# Clock.net
KiCad netlist of a schematic drawn in EAGLE
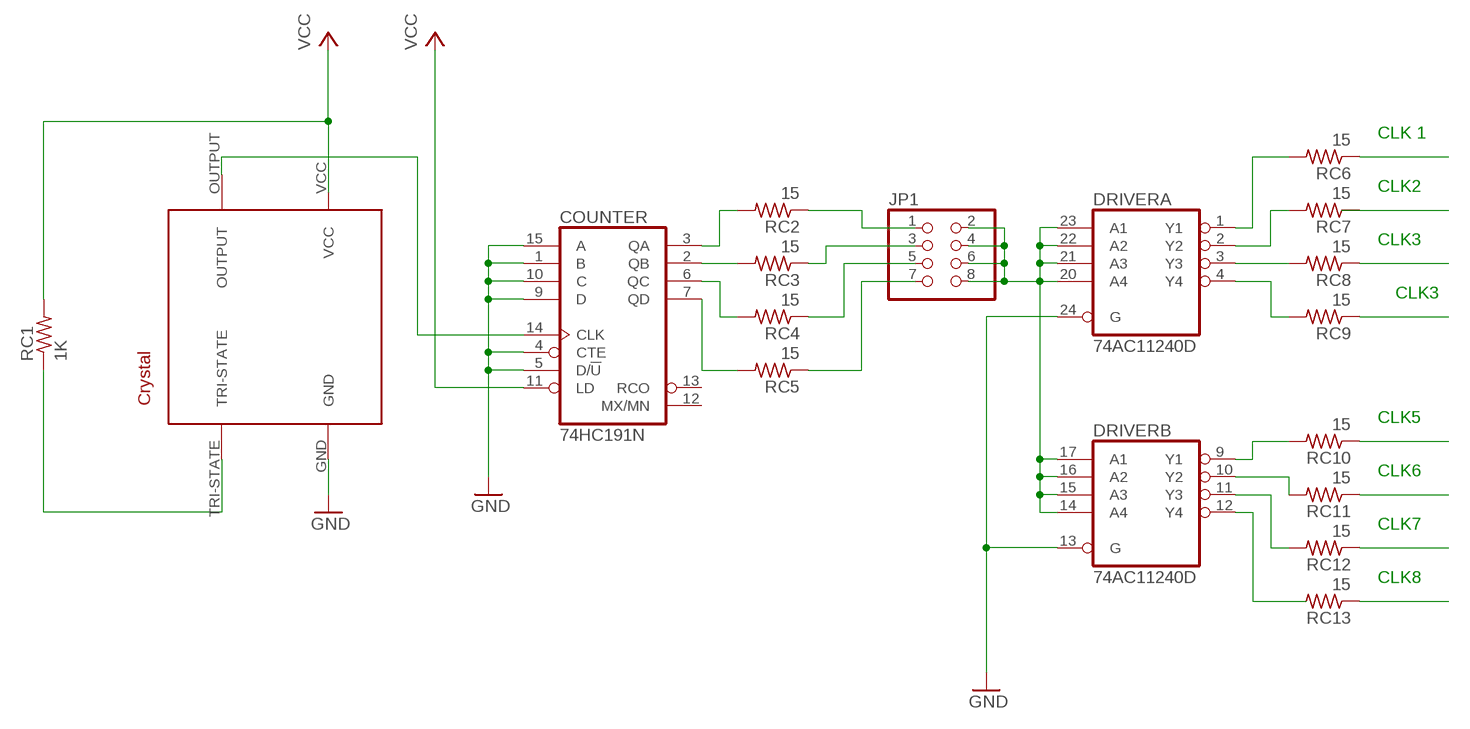
[diagram p0: schematic, sheet 1]

(export (version "E")
  (design (tool "Eeschema 10.0.6"))
  (components
    (comp (ref "COUNTER")
      (value "74HC191N")
      (footprint "eagle-import:DIL16")
      (libsource (lib "eagle-import") (part "74191NHC"))
    )
    (comp (ref "DRIVER")
      (value "74AC11240D")
      (footprint "eagle-import:SO24W")
      (libsource (lib "eagle-import") (part "74AC11240D"))
    )
    (comp (ref "JP1")
      (value "PINHD-2X4")
      (footprint "eagle-import:2X04")
      (libsource (lib "eagle-import") (part "PINHD-2X4"))
    )
    (comp (ref "RC1")
      (value "1K")
      (footprint "eagle-import:R0805")
      (libsource (lib "eagle-import") (part "R-US_R0805"))
    )
    (comp (ref "RC2")
      (value "15")
      (footprint "eagle-import:R0805")
      (libsource (lib "eagle-import") (part "R-US_R0805"))
    )
    (comp (ref "RC3")
      (value "15")
      (footprint "eagle-import:R0805")
      (libsource (lib "eagle-import") (part "R-US_R0805"))
    )
    (comp (ref "RC4")
      (value "15")
      (footprint "eagle-import:R0805")
      (libsource (lib "eagle-import") (part "R-US_R0805"))
    )
    (comp (ref "RC5")
      (value "15")
      (footprint "eagle-import:R0805")
      (libsource (lib "eagle-import") (part "R-US_R0805"))
    )
    (comp (ref "RC6")
      (value "15")
      (footprint "eagle-import:R0805")
      (libsource (lib "eagle-import") (part "R-US_R0805"))
    )
    (comp (ref "RC7")
      (value "15")
      (footprint "eagle-import:R0805")
      (libsource (lib "eagle-import") (part "R-US_R0805"))
    )
    (comp (ref "RC8")
      (value "15")
      (footprint "eagle-import:R0805")
      (libsource (lib "eagle-import") (part "R-US_R0805"))
    )
    (comp (ref "RC9")
      (value "15")
      (footprint "eagle-import:R0805")
      (libsource (lib "eagle-import") (part "R-US_R0805"))
    )
    (comp (ref "RC10")
      (value "15")
      (footprint "eagle-import:R0805")
      (libsource (lib "eagle-import") (part "R-US_R0805"))
    )
    (comp (ref "RC11")
      (value "15")
      (footprint "eagle-import:R0805")
      (libsource (lib "eagle-import") (part "R-US_R0805"))
    )
    (comp (ref "RC12")
      (value "15")
      (footprint "eagle-import:R0805")
      (libsource (lib "eagle-import") (part "R-US_R0805"))
    )
    (comp (ref "RC13")
      (value "15")
      (footprint "eagle-import:R0805")
      (libsource (lib "eagle-import") (part "R-US_R0805"))
    )
    (comp (ref "U$1")
      (value "ECS-8FX")
      (footprint "eagle-import:ECS-8FX")
      (libsource (lib "eagle-import") (part "ECS-8FX"))
    )
  )
  (nets
    (net (code "1") (name "GND") (class "Default")
      (node (ref "COUNTER") (pin "1") (pinfunction "B_1") (pintype "input"))
      (node (ref "COUNTER") (pin "10") (pinfunction "C_10") (pintype "input"))
      (node (ref "COUNTER") (pin "15") (pinfunction "A_15") (pintype "input"))
      (node (ref "COUNTER") (pin "4") (pinfunction "CTE_4") (pintype "input"))
      (node (ref "COUNTER") (pin "5") (pinfunction "D/~{U}_5") (pintype "input"))
      (node (ref "COUNTER") (pin "9") (pinfunction "D_9") (pintype "input"))
      (node (ref "DRIVER") (pin "13") (pinfunction "G_13") (pintype "input"))
      (node (ref "DRIVER") (pin "24") (pinfunction "G_24") (pintype "input"))
      (node (ref "U$1") (pin "GND") (pinfunction "GND_GND") (pintype "bidirectional"))
    )
    (net (code "2") (name "Net-(COUNTERA-CLK)") (class "Default")
      (node (ref "COUNTER") (pin "14") (pinfunction "CLK_14") (pintype "input"))
      (node (ref "U$1") (pin "OUTPUT") (pinfunction "OUTPUT_OUTPUT") (pintype "bidirectional"))
    )
    (net (code "3") (name "Net-(COUNTERA-QA)") (class "Default")
      (node (ref "COUNTER") (pin "3") (pinfunction "QA_3") (pintype "output"))
      (node (ref "RC2") (pin "2") (pinfunction "2_2") (pintype "passive"))
    )
    (net (code "4") (name "Net-(COUNTERA-QB)") (class "Default")
      (node (ref "COUNTER") (pin "2") (pinfunction "QB_2") (pintype "output"))
      (node (ref "RC3") (pin "2") (pinfunction "2_2") (pintype "passive"))
    )
    (net (code "5") (name "Net-(COUNTERA-QC)") (class "Default")
      (node (ref "COUNTER") (pin "6") (pinfunction "QC_6") (pintype "output"))
      (node (ref "RC4") (pin "2") (pinfunction "2_2") (pintype "passive"))
    )
    (net (code "6") (name "Net-(COUNTERA-QD)") (class "Default")
      (node (ref "COUNTER") (pin "7") (pinfunction "QD_7") (pintype "output"))
      (node (ref "RC5") (pin "2") (pinfunction "2_2") (pintype "passive"))
    )
    (net (code "7") (name "Net-(DRIVERA-A1)") (class "Default")
      (node (ref "DRIVER") (pin "14") (pinfunction "A4_14") (pintype "input"))
      (node (ref "DRIVER") (pin "15") (pinfunction "A3_15") (pintype "input"))
      (node (ref "DRIVER") (pin "16") (pinfunction "A2_16") (pintype "input"))
      (node (ref "DRIVER") (pin "17") (pinfunction "A1_17") (pintype "input"))
      (node (ref "DRIVER") (pin "20") (pinfunction "A4_20") (pintype "input"))
      (node (ref "DRIVER") (pin "21") (pinfunction "A3_21") (pintype "input"))
      (node (ref "DRIVER") (pin "22") (pinfunction "A2_22") (pintype "input"))
      (node (ref "DRIVER") (pin "23") (pinfunction "A1_23") (pintype "input"))
      (node (ref "JP1") (pin "2") (pinfunction "2_2") (pintype "passive"))
      (node (ref "JP1") (pin "4") (pinfunction "4_4") (pintype "passive"))
      (node (ref "JP1") (pin "6") (pinfunction "6_6") (pintype "passive"))
      (node (ref "JP1") (pin "8") (pinfunction "8_8") (pintype "passive"))
    )
    (net (code "8") (name "Net-(DRIVERA-Y1)") (class "Default")
      (node (ref "DRIVER") (pin "1") (pinfunction "Y1_1") (pintype "tri_state"))
      (node (ref "RC6") (pin "2") (pinfunction "2_2") (pintype "passive"))
    )
    (net (code "9") (name "Net-(DRIVERA-Y2)") (class "Default")
      (node (ref "DRIVER") (pin "2") (pinfunction "Y2_2") (pintype "tri_state"))
      (node (ref "RC7") (pin "2") (pinfunction "2_2") (pintype "passive"))
    )
    (net (code "10") (name "Net-(DRIVERA-Y3)") (class "Default")
      (node (ref "DRIVER") (pin "3") (pinfunction "Y3_3") (pintype "tri_state"))
      (node (ref "RC8") (pin "2") (pinfunction "2_2") (pintype "passive"))
    )
    (net (code "11") (name "Net-(DRIVERA-Y4)") (class "Default")
      (node (ref "DRIVER") (pin "4") (pinfunction "Y4_4") (pintype "tri_state"))
      (node (ref "RC9") (pin "2") (pinfunction "2_2") (pintype "passive"))
    )
    (net (code "12") (name "Net-(DRIVERB-Y1)") (class "Default")
      (node (ref "DRIVER") (pin "9") (pinfunction "Y1_9") (pintype "tri_state"))
      (node (ref "RC10") (pin "2") (pinfunction "2_2") (pintype "passive"))
    )
    (net (code "13") (name "Net-(DRIVERB-Y2)") (class "Default")
      (node (ref "DRIVER") (pin "10") (pinfunction "Y2_10") (pintype "tri_state"))
      (node (ref "RC11") (pin "2") (pinfunction "2_2") (pintype "passive"))
    )
    (net (code "14") (name "Net-(DRIVERB-Y3)") (class "Default")
      (node (ref "DRIVER") (pin "11") (pinfunction "Y3_11") (pintype "tri_state"))
      (node (ref "RC12") (pin "2") (pinfunction "2_2") (pintype "passive"))
    )
    (net (code "15") (name "Net-(JP1-Pad1)") (class "Default")
      (node (ref "JP1") (pin "1") (pinfunction "1_1") (pintype "passive"))
      (node (ref "RC2") (pin "1") (pinfunction "1_1") (pintype "passive"))
    )
    (net (code "16") (name "Net-(JP1-Pad3)") (class "Default")
      (node (ref "JP1") (pin "3") (pinfunction "3_3") (pintype "passive"))
      (node (ref "RC3") (pin "1") (pinfunction "1_1") (pintype "passive"))
    )
    (net (code "17") (name "Net-(JP1-Pad5)") (class "Default")
      (node (ref "JP1") (pin "5") (pinfunction "5_5") (pintype "passive"))
      (node (ref "RC4") (pin "1") (pinfunction "1_1") (pintype "passive"))
    )
    (net (code "18") (name "Net-(JP1-Pad7)") (class "Default")
      (node (ref "JP1") (pin "7") (pinfunction "7_7") (pintype "passive"))
      (node (ref "RC5") (pin "1") (pinfunction "1_1") (pintype "passive"))
    )
    (net (code "19") (name "Net-(RC1-Pad1)") (class "Default")
      (node (ref "RC1") (pin "1") (pinfunction "1_1") (pintype "passive"))
      (node (ref "U$1") (pin "TRI-STATE") (pinfunction "TRI-STATE_TRI-STATE") (pintype "bidirectional"))
    )
    (net (code "20") (name "VCC") (class "Default")
      (node (ref "COUNTER") (pin "11") (pinfunction "LD_11") (pintype "input"))
      (node (ref "RC1") (pin "2") (pinfunction "2_2") (pintype "passive"))
    )
    (net (code "21") (name "unconnected-(COUNTERA-MX{slash}MN-Pad12)") (class "Default")
      (node (ref "COUNTER") (pin "12") (pinfunction "MX/MN_12") (pintype "output"))
    )
    (net (code "22") (name "unconnected-(COUNTERA-RCO-Pad13)") (class "Default")
      (node (ref "COUNTER") (pin "13") (pinfunction "RCO_13") (pintype "output"))
    )
    (net (code "23") (name "unconnected-(DRIVERB-Y4-Pad12)") (class "Default")
      (node (ref "DRIVER") (pin "12") (pinfunction "Y4_12") (pintype "tri_state"))
    )
    (net (code "24") (name "unconnected-(RC6-Pad1)") (class "Default")
      (node (ref "RC6") (pin "1") (pinfunction "1_1") (pintype "passive"))
    )
    (net (code "25") (name "unconnected-(RC7-Pad1)") (class "Default")
      (node (ref "RC7") (pin "1") (pinfunction "1_1") (pintype "passive"))
    )
    (net (code "26") (name "unconnected-(RC8-Pad1)") (class "Default")
      (node (ref "RC8") (pin "1") (pinfunction "1_1") (pintype "passive"))
    )
    (net (code "27") (name "unconnected-(RC9-Pad1)") (class "Default")
      (node (ref "RC9") (pin "1") (pinfunction "1_1") (pintype "passive"))
    )
    (net (code "28") (name "unconnected-(RC10-Pad1)") (class "Default")
      (node (ref "RC10") (pin "1") (pinfunction "1_1") (pintype "passive"))
    )
    (net (code "29") (name "unconnected-(RC11-Pad1)") (class "Default")
      (node (ref "RC11") (pin "1") (pinfunction "1_1") (pintype "passive"))
    )
    (net (code "30") (name "unconnected-(RC12-Pad1)") (class "Default")
      (node (ref "RC12") (pin "1") (pinfunction "1_1") (pintype "passive"))
    )
    (net (code "31") (name "unconnected-(RC13-Pad1)") (class "Default")
      (node (ref "RC13") (pin "1") (pinfunction "1_1") (pintype "passive"))
    )
    (net (code "32") (name "unconnected-(RC13-Pad2)") (class "Default")
      (node (ref "RC13") (pin "2") (pinfunction "2_2") (pintype "passive"))
    )
    (net (code "33") (name "unconnected-(U$1-PadVCC)") (class "Default")
      (node (ref "U$1") (pin "VCC") (pinfunction "VCC_VCC") (pintype "bidirectional"))
    )
  )
)
